# SwitchBypass.net
KiCad netlist of a schematic drawn in EAGLE
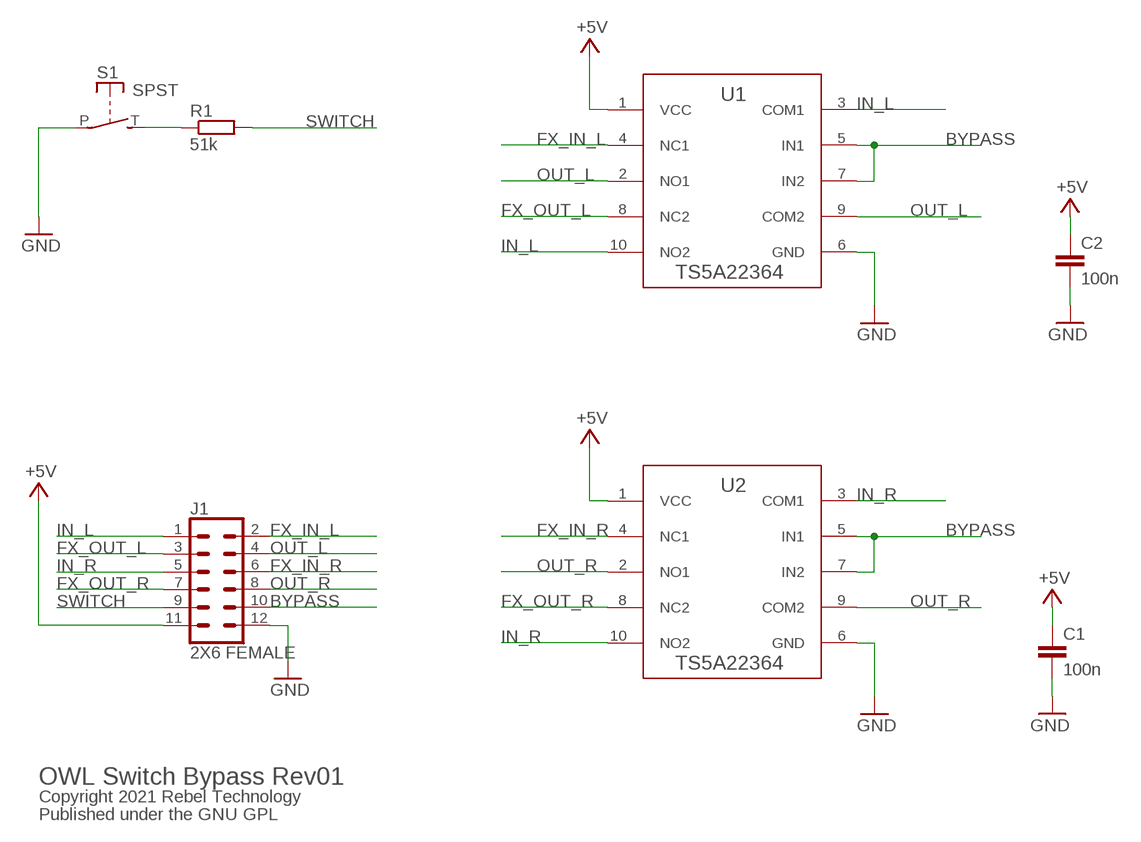
[diagram p0: schematic, sheet 1]

(export (version "E")
  (design (tool "Eeschema 10.0.6"))
  (components
    (comp (ref "C1")
      (value "100n")
      (footprint "eagle-import:C0603")
      (libsource (lib "eagle-import") (part "C-EUC0603"))
    )
    (comp (ref "C2")
      (value "100n")
      (footprint "eagle-import:C0603")
      (libsource (lib "eagle-import") (part "C-EUC0603"))
    )
    (comp (ref "J1")
      (value "2X6 FEMALE")
      (footprint "eagle-import:2X6")
      (libsource (lib "eagle-import") (part "CONN_06X2PTH_FEMALE"))
    )
    (comp (ref "R1")
      (value "51k")
      (footprint "eagle-import:0603")
      (libsource (lib "eagle-import") (part "R-EU_0603"))
    )
    (comp (ref "S1")
      (value "SPST")
      (footprint "eagle-import:JUDCOSPST")
      (libsource (lib "eagle-import") (part "SPST"))
    )
    (comp (ref "U1")
      (value "TS5A22364")
      (footprint "eagle-import:DGS0010A_L")
      (fields (field (name "MANUFACTURER") "Texas Instruments") (field (name "PARTNUMBER") "TS5A22364DGSR"))
      (libsource (lib "eagle-import") (part "TS5A22364DGSRDGS0010A_L"))
    )
    (comp (ref "U2")
      (value "TS5A22364")
      (footprint "eagle-import:DGS0010A_L")
      (fields (field (name "MANUFACTURER") "Texas Instruments") (field (name "PARTNUMBER") "TS5A22364DGSR"))
      (libsource (lib "eagle-import") (part "TS5A22364DGSRDGS0010A_L"))
    )
  )
  (nets
    (net (code "1") (name "+5V") (class "Default")
      (node (ref "C1") (pin "1") (pinfunction "1_1") (pintype "passive"))
      (node (ref "C2") (pin "1") (pinfunction "1_1") (pintype "passive"))
      (node (ref "J1") (pin "11") (pinfunction "11_11") (pintype "passive"))
      (node (ref "U1") (pin "1") (pinfunction "VCC_1") (pintype "power_in"))
      (node (ref "U2") (pin "1") (pinfunction "VCC_1") (pintype "power_in"))
    )
    (net (code "2") (name "/BYPASS") (class "Default")
      (node (ref "J1") (pin "10") (pinfunction "10_10") (pintype "passive"))
      (node (ref "U1") (pin "5") (pinfunction "IN1_5") (pintype "input"))
      (node (ref "U1") (pin "7") (pinfunction "IN2_7") (pintype "input"))
      (node (ref "U2") (pin "5") (pinfunction "IN1_5") (pintype "input"))
      (node (ref "U2") (pin "7") (pinfunction "IN2_7") (pintype "input"))
    )
    (net (code "3") (name "/FX_IN_L") (class "Default")
      (node (ref "J1") (pin "2") (pinfunction "2_2") (pintype "passive"))
      (node (ref "U1") (pin "4") (pinfunction "NC1_4") (pintype "passive"))
    )
    (net (code "4") (name "/FX_IN_R") (class "Default")
      (node (ref "J1") (pin "6") (pinfunction "6_6") (pintype "passive"))
      (node (ref "U2") (pin "4") (pinfunction "NC1_4") (pintype "passive"))
    )
    (net (code "5") (name "/FX_OUT_L") (class "Default")
      (node (ref "J1") (pin "3") (pinfunction "3_3") (pintype "passive"))
      (node (ref "U1") (pin "8") (pinfunction "NC2_8") (pintype "passive"))
    )
    (net (code "6") (name "/FX_OUT_R") (class "Default")
      (node (ref "J1") (pin "7") (pinfunction "7_7") (pintype "passive"))
      (node (ref "U2") (pin "8") (pinfunction "NC2_8") (pintype "passive"))
    )
    (net (code "7") (name "/IN_L") (class "Default")
      (node (ref "J1") (pin "1") (pinfunction "1_1") (pintype "passive"))
      (node (ref "U1") (pin "10") (pinfunction "NO2_10") (pintype "passive"))
      (node (ref "U1") (pin "3") (pinfunction "COM1_3") (pintype "passive"))
    )
    (net (code "8") (name "/IN_R") (class "Default")
      (node (ref "J1") (pin "5") (pinfunction "5_5") (pintype "passive"))
      (node (ref "U2") (pin "10") (pinfunction "NO2_10") (pintype "passive"))
      (node (ref "U2") (pin "3") (pinfunction "COM1_3") (pintype "passive"))
    )
    (net (code "9") (name "/OUT_L") (class "Default")
      (node (ref "J1") (pin "4") (pinfunction "4_4") (pintype "passive"))
      (node (ref "U1") (pin "2") (pinfunction "NO1_2") (pintype "passive"))
      (node (ref "U1") (pin "9") (pinfunction "COM2_9") (pintype "passive"))
    )
    (net (code "10") (name "/OUT_R") (class "Default")
      (node (ref "J1") (pin "8") (pinfunction "8_8") (pintype "passive"))
      (node (ref "U2") (pin "2") (pinfunction "NO1_2") (pintype "passive"))
      (node (ref "U2") (pin "9") (pinfunction "COM2_9") (pintype "passive"))
    )
    (net (code "11") (name "/SWITCH") (class "Default")
      (node (ref "J1") (pin "9") (pinfunction "9_9") (pintype "passive"))
      (node (ref "R1") (pin "2") (pinfunction "2_2") (pintype "passive"))
    )
    (net (code "12") (name "GND") (class "Default")
      (node (ref "C1") (pin "2") (pinfunction "2_2") (pintype "passive"))
      (node (ref "C2") (pin "2") (pinfunction "2_2") (pintype "passive"))
      (node (ref "J1") (pin "12") (pinfunction "12_12") (pintype "passive"))
      (node (ref "S1") (pin "P") (pinfunction "P_P") (pintype "passive"))
      (node (ref "U1") (pin "6") (pinfunction "GND_6") (pintype "power_in"))
      (node (ref "U2") (pin "6") (pinfunction "GND_6") (pintype "power_in"))
    )
    (net (code "13") (name "Net-(S1-S)") (class "Default")
      (node (ref "R1") (pin "1") (pinfunction "1_1") (pintype "passive"))
      (node (ref "S1") (pin "T") (pinfunction "S_T") (pintype "passive"))
    )
  )
)
